# DSP2.net
KiCad netlist of a schematic drawn in Altium Designer
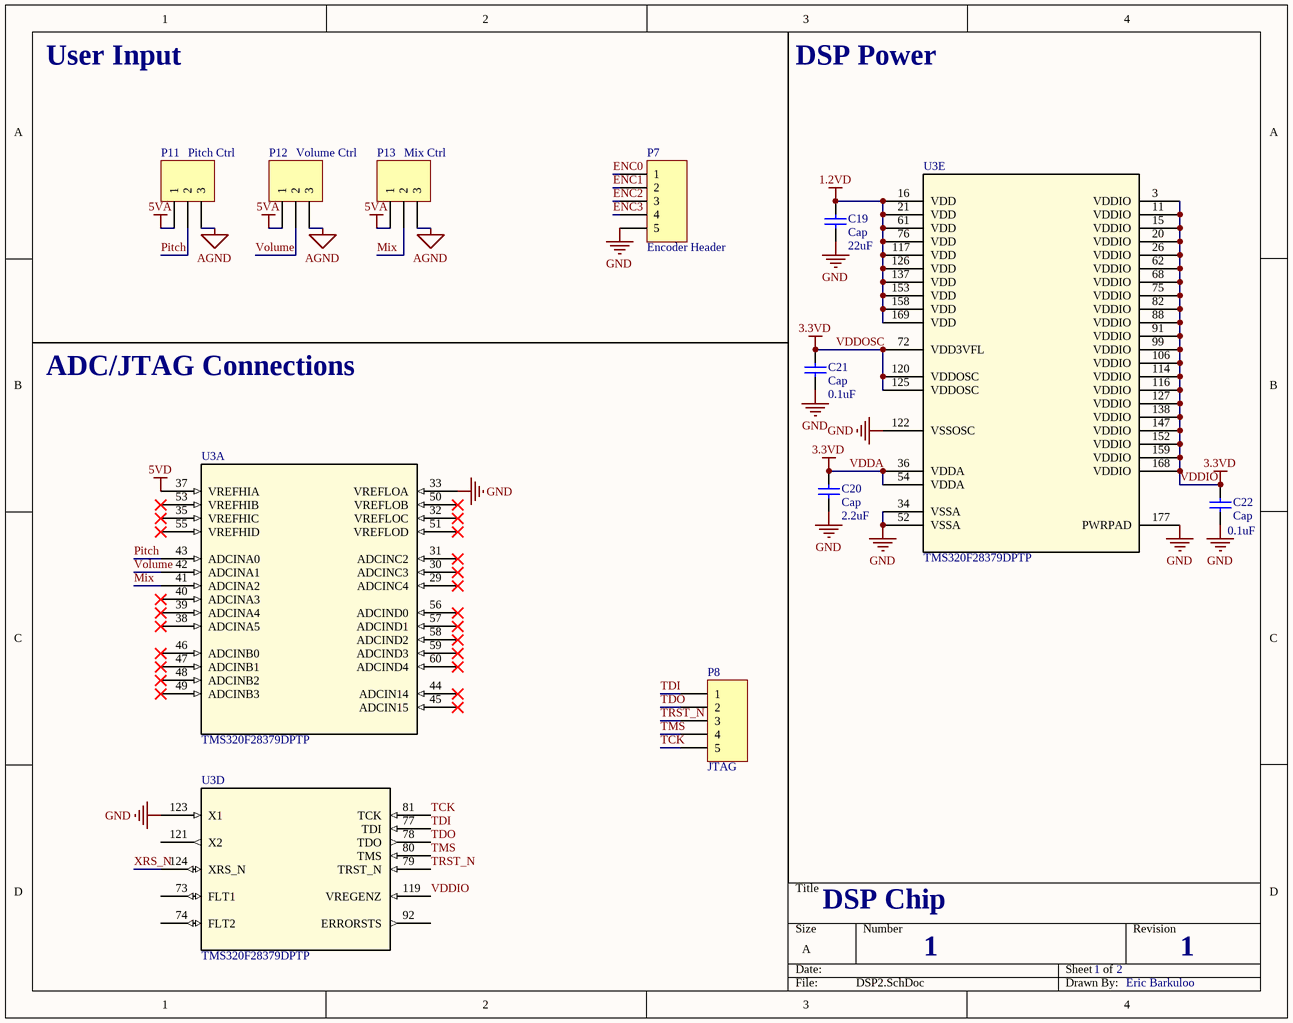
[diagram p0: DSP2.SchDoc]

(export (version "E")
  (design (tool "Eeschema 10.0.6"))
  (components
    (comp (ref "C19")
      (value "Cap")
      (footprint "Passives:CAPC0805")
      (description "Capacitor")
      (fields (field (name "ALTIUM_VALUE") "22uF") (field (name "PUBLISHER") "Altium Limited"))
      (libsource (lib "Miscellaneous Devices") (part "Cap"))
    )
    (comp (ref "C20")
      (value "Cap")
      (footprint "Passives:CAPC0805")
      (description "Capacitor")
      (fields (field (name "ALTIUM_VALUE") "2.2uF") (field (name "PUBLISHER") "Altium Limited"))
      (libsource (lib "Miscellaneous Devices") (part "Cap"))
    )
    (comp (ref "C21")
      (value "Cap")
      (footprint "Passives:CAPC0805")
      (description "Capacitor")
      (fields (field (name "ALTIUM_VALUE") "0.1uF") (field (name "PUBLISHER") "Altium Limited"))
      (libsource (lib "Miscellaneous Devices") (part "Cap"))
    )
    (comp (ref "C22")
      (value "Cap")
      (footprint "Passives:CAPC0805")
      (description "Capacitor")
      (fields (field (name "ALTIUM_VALUE") "0.1uF") (field (name "PUBLISHER") "Altium Limited"))
      (libsource (lib "Miscellaneous Devices") (part "Cap"))
    )
    (comp (ref "P7")
      (value "Encoder Header")
      (footprint "HDR1X5")
      (description "Header, 5-Pin")
      (fields (field (name "PUBLISHER") "Altium Limited"))
      (libsource (lib "Miscellaneous Connectors") (part "Header 5"))
    )
    (comp (ref "P8")
      (value "JTAG")
      (footprint "HDR1X5")
      (description "Header, 5-Pin")
      (fields (field (name "PUBLISHER") "Altium Limited"))
      (libsource (lib "Miscellaneous Connectors") (part "Header 5"))
    )
    (comp (ref "P11")
      (value "Pitch Ctrl")
      (footprint "HDR1X3")
      (description "Header, 3-Pin")
      (fields (field (name "PUBLISHER") "Altium Limited"))
      (libsource (lib "Miscellaneous Connectors") (part "Header 3"))
    )
    (comp (ref "P12")
      (value "Volume Ctrl")
      (footprint "HDR1X3")
      (description "Header, 3-Pin")
      (fields (field (name "PUBLISHER") "Altium Limited"))
      (libsource (lib "Miscellaneous Connectors") (part "Header 3"))
    )
    (comp (ref "P13")
      (value "Mix Ctrl")
      (footprint "HDR1X3")
      (description "Header, 3-Pin")
      (fields (field (name "PUBLISHER") "Altium Limited"))
      (libsource (lib "Miscellaneous Connectors") (part "Header 3"))
    )
    (comp (ref "U3")
      (value "TMS320F28379DPTP")
      (footprint "TMS320F28379DPTPT:PTP0176F_N")
      (description "Imported")
      (fields
        (field (name "PARTNUMBER") "TMS320F28379DPTPS")
        (field (name "MANUFACTURER") "Texas Instruments")
      )
      (libsource (lib "TMS320F28379DPTPT") (part "TMS320F28379DPTP"))
    )
  )
  (nets
    (net (code "1") (name "/ENC0") (class "Default")
      (node (ref "P7") (pin "1") (pinfunction "1_1") (pintype "passive"))
    )
    (net (code "2") (name "/ENC1") (class "Default")
      (node (ref "P7") (pin "2") (pinfunction "2_2") (pintype "passive"))
    )
    (net (code "3") (name "/ENC2") (class "Default")
      (node (ref "P7") (pin "3") (pinfunction "3_3") (pintype "passive"))
    )
    (net (code "4") (name "/ENC3") (class "Default")
      (node (ref "P7") (pin "4") (pinfunction "4_4") (pintype "passive"))
    )
    (net (code "5") (name "/Mix") (class "Default")
      (node (ref "P13") (pin "2") (pinfunction "2_2") (pintype "passive"))
      (node (ref "U3") (pin "41") (pinfunction "ADCINA2_41") (pintype "input"))
    )
    (net (code "6") (name "/Pitch") (class "Default")
      (node (ref "P11") (pin "2") (pinfunction "2_2") (pintype "passive"))
      (node (ref "U3") (pin "43") (pinfunction "ADCINA0_43") (pintype "input"))
    )
    (net (code "7") (name "/TCK") (class "Default")
      (node (ref "P8") (pin "5") (pinfunction "5_5") (pintype "passive"))
      (node (ref "U3") (pin "81") (pinfunction "TCK_81") (pintype "input"))
    )
    (net (code "8") (name "/TDI") (class "Default")
      (node (ref "P8") (pin "1") (pinfunction "1_1") (pintype "passive"))
      (node (ref "U3") (pin "77") (pinfunction "TDI_77") (pintype "input"))
    )
    (net (code "9") (name "/TDO") (class "Default")
      (node (ref "P8") (pin "2") (pinfunction "2_2") (pintype "passive"))
      (node (ref "U3") (pin "78") (pinfunction "TDO_78") (pintype "output"))
    )
    (net (code "10") (name "/TMS") (class "Default")
      (node (ref "P8") (pin "4") (pinfunction "4_4") (pintype "passive"))
      (node (ref "U3") (pin "80") (pinfunction "TMS_80") (pintype "input"))
    )
    (net (code "11") (name "/TRST_N") (class "Default")
      (node (ref "P8") (pin "3") (pinfunction "3_3") (pintype "passive"))
      (node (ref "U3") (pin "79") (pinfunction "TRST_N_79") (pintype "input"))
    )
    (net (code "12") (name "/Volume") (class "Default")
      (node (ref "P12") (pin "2") (pinfunction "2_2") (pintype "passive"))
      (node (ref "U3") (pin "42") (pinfunction "ADCINA1_42") (pintype "input"))
    )
    (net (code "13") (name "/XRS_N") (class "Default")
      (node (ref "U3") (pin "124") (pinfunction "XRS_N_124") (pintype "bidirectional"))
    )
    (net (code "14") (name "1.2VD") (class "Default")
      (node (ref "C19") (pin "2") (pinfunction "2_2") (pintype "passive"))
      (node (ref "U3") (pin "117") (pinfunction "VDD_117") (pintype "power_in"))
      (node (ref "U3") (pin "126") (pinfunction "VDD_126") (pintype "power_in"))
      (node (ref "U3") (pin "137") (pinfunction "VDD_137") (pintype "power_in"))
      (node (ref "U3") (pin "153") (pinfunction "VDD_153") (pintype "power_in"))
      (node (ref "U3") (pin "158") (pinfunction "VDD_158") (pintype "power_in"))
      (node (ref "U3") (pin "16") (pinfunction "VDD_16") (pintype "power_in"))
      (node (ref "U3") (pin "169") (pinfunction "VDD_169") (pintype "power_in"))
      (node (ref "U3") (pin "21") (pinfunction "VDD_21") (pintype "power_in"))
      (node (ref "U3") (pin "61") (pinfunction "VDD_61") (pintype "power_in"))
      (node (ref "U3") (pin "76") (pinfunction "VDD_76") (pintype "power_in"))
    )
    (net (code "15") (name "3.3VD") (class "Default")
      (node (ref "C20") (pin "2") (pinfunction "2_2") (pintype "passive"))
      (node (ref "C21") (pin "2") (pinfunction "2_2") (pintype "passive"))
      (node (ref "C22") (pin "2") (pinfunction "2_2") (pintype "passive"))
      (node (ref "U3") (pin "106") (pinfunction "VDDIO_106") (pintype "power_in"))
      (node (ref "U3") (pin "11") (pinfunction "VDDIO_11") (pintype "power_in"))
      (node (ref "U3") (pin "114") (pinfunction "VDDIO_114") (pintype "power_in"))
      (node (ref "U3") (pin "116") (pinfunction "VDDIO_116") (pintype "power_in"))
      (node (ref "U3") (pin "119") (pinfunction "VREGENZ_119") (pintype "input"))
      (node (ref "U3") (pin "120") (pinfunction "VDDOSC_120") (pintype "power_in"))
      (node (ref "U3") (pin "125") (pinfunction "VDDOSC_125") (pintype "power_in"))
      (node (ref "U3") (pin "127") (pinfunction "VDDIO_127") (pintype "power_in"))
      (node (ref "U3") (pin "138") (pinfunction "VDDIO_138") (pintype "power_in"))
      (node (ref "U3") (pin "147") (pinfunction "VDDIO_147") (pintype "power_in"))
      (node (ref "U3") (pin "15") (pinfunction "VDDIO_15") (pintype "power_in"))
      (node (ref "U3") (pin "152") (pinfunction "VDDIO_152") (pintype "power_in"))
      (node (ref "U3") (pin "159") (pinfunction "VDDIO_159") (pintype "power_in"))
      (node (ref "U3") (pin "168") (pinfunction "VDDIO_168") (pintype "power_in"))
      (node (ref "U3") (pin "20") (pinfunction "VDDIO_20") (pintype "power_in"))
      (node (ref "U3") (pin "26") (pinfunction "VDDIO_26") (pintype "power_in"))
      (node (ref "U3") (pin "3") (pinfunction "VDDIO_3") (pintype "power_in"))
      (node (ref "U3") (pin "36") (pinfunction "VDDA_36") (pintype "power_in"))
      (node (ref "U3") (pin "54") (pinfunction "VDDA_54") (pintype "power_in"))
      (node (ref "U3") (pin "62") (pinfunction "VDDIO_62") (pintype "power_in"))
      (node (ref "U3") (pin "68") (pinfunction "VDDIO_68") (pintype "power_in"))
      (node (ref "U3") (pin "72") (pinfunction "VDD3VFL_72") (pintype "power_in"))
      (node (ref "U3") (pin "75") (pinfunction "VDDIO_75") (pintype "power_in"))
      (node (ref "U3") (pin "82") (pinfunction "VDDIO_82") (pintype "power_in"))
      (node (ref "U3") (pin "88") (pinfunction "VDDIO_88") (pintype "power_in"))
      (node (ref "U3") (pin "91") (pinfunction "VDDIO_91") (pintype "power_in"))
      (node (ref "U3") (pin "99") (pinfunction "VDDIO_99") (pintype "power_in"))
    )
    (net (code "16") (name "5VA") (class "Default")
      (node (ref "P11") (pin "1") (pinfunction "1_1") (pintype "passive"))
      (node (ref "P12") (pin "1") (pinfunction "1_1") (pintype "passive"))
      (node (ref "P13") (pin "1") (pinfunction "1_1") (pintype "passive"))
    )
    (net (code "17") (name "5VD") (class "Default")
      (node (ref "U3") (pin "37") (pinfunction "VREFHIA_37") (pintype "input"))
    )
    (net (code "18") (name "AGND") (class "Default")
      (node (ref "P11") (pin "3") (pinfunction "3_3") (pintype "passive"))
      (node (ref "P12") (pin "3") (pinfunction "3_3") (pintype "passive"))
      (node (ref "P13") (pin "3") (pinfunction "3_3") (pintype "passive"))
    )
    (net (code "19") (name "GND") (class "Default")
      (node (ref "C19") (pin "1") (pinfunction "1_1") (pintype "passive"))
      (node (ref "C20") (pin "1") (pinfunction "1_1") (pintype "passive"))
      (node (ref "C21") (pin "1") (pinfunction "1_1") (pintype "passive"))
      (node (ref "C22") (pin "1") (pinfunction "1_1") (pintype "passive"))
      (node (ref "P7") (pin "5") (pinfunction "5_5") (pintype "passive"))
      (node (ref "U3") (pin "122") (pinfunction "VSSOSC_122") (pintype "power_in"))
      (node (ref "U3") (pin "123") (pinfunction "X1_123") (pintype "input"))
      (node (ref "U3") (pin "177") (pinfunction "PWRPAD_177") (pintype "power_in"))
      (node (ref "U3") (pin "33") (pinfunction "VREFLOA_33") (pintype "input"))
      (node (ref "U3") (pin "34") (pinfunction "VSSA_34") (pintype "power_in"))
      (node (ref "U3") (pin "52") (pinfunction "VSSA_52") (pintype "power_in"))
    )
    (net (code "20") (name "unconnected-(U3A-ADCIN14-Pad44)") (class "Default")
      (node (ref "U3") (pin "44") (pinfunction "ADCIN14_44") (pintype "input+no_connect"))
    )
    (net (code "21") (name "unconnected-(U3A-ADCIN15-Pad45)") (class "Default")
      (node (ref "U3") (pin "45") (pinfunction "ADCIN15_45") (pintype "input+no_connect"))
    )
    (net (code "22") (name "unconnected-(U3A-ADCINA3-Pad40)") (class "Default")
      (node (ref "U3") (pin "40") (pinfunction "ADCINA3_40") (pintype "input+no_connect"))
    )
    (net (code "23") (name "unconnected-(U3A-ADCINA4-Pad39)") (class "Default")
      (node (ref "U3") (pin "39") (pinfunction "ADCINA4_39") (pintype "input+no_connect"))
    )
    (net (code "24") (name "unconnected-(U3A-ADCINA5-Pad38)") (class "Default")
      (node (ref "U3") (pin "38") (pinfunction "ADCINA5_38") (pintype "input+no_connect"))
    )
    (net (code "25") (name "unconnected-(U3A-ADCINB0-Pad46)") (class "Default")
      (node (ref "U3") (pin "46") (pinfunction "ADCINB0_46") (pintype "input+no_connect"))
    )
    (net (code "26") (name "unconnected-(U3A-ADCINB1-Pad47)") (class "Default")
      (node (ref "U3") (pin "47") (pinfunction "ADCINB1_47") (pintype "input+no_connect"))
    )
    (net (code "27") (name "unconnected-(U3A-ADCINB2-Pad48)") (class "Default")
      (node (ref "U3") (pin "48") (pinfunction "ADCINB2_48") (pintype "input+no_connect"))
    )
    (net (code "28") (name "unconnected-(U3A-ADCINB3-Pad49)") (class "Default")
      (node (ref "U3") (pin "49") (pinfunction "ADCINB3_49") (pintype "input+no_connect"))
    )
    (net (code "29") (name "unconnected-(U3A-ADCINC2-Pad31)") (class "Default")
      (node (ref "U3") (pin "31") (pinfunction "ADCINC2_31") (pintype "input+no_connect"))
    )
    (net (code "30") (name "unconnected-(U3A-ADCINC3-Pad30)") (class "Default")
      (node (ref "U3") (pin "30") (pinfunction "ADCINC3_30") (pintype "input+no_connect"))
    )
    (net (code "31") (name "unconnected-(U3A-ADCINC4-Pad29)") (class "Default")
      (node (ref "U3") (pin "29") (pinfunction "ADCINC4_29") (pintype "input+no_connect"))
    )
    (net (code "32") (name "unconnected-(U3A-ADCIND0-Pad56)") (class "Default")
      (node (ref "U3") (pin "56") (pinfunction "ADCIND0_56") (pintype "input+no_connect"))
    )
    (net (code "33") (name "unconnected-(U3A-ADCIND1-Pad57)") (class "Default")
      (node (ref "U3") (pin "57") (pinfunction "ADCIND1_57") (pintype "input+no_connect"))
    )
    (net (code "34") (name "unconnected-(U3A-ADCIND2-Pad58)") (class "Default")
      (node (ref "U3") (pin "58") (pinfunction "ADCIND2_58") (pintype "input+no_connect"))
    )
    (net (code "35") (name "unconnected-(U3A-ADCIND3-Pad59)") (class "Default")
      (node (ref "U3") (pin "59") (pinfunction "ADCIND3_59") (pintype "input+no_connect"))
    )
    (net (code "36") (name "unconnected-(U3A-ADCIND4-Pad60)") (class "Default")
      (node (ref "U3") (pin "60") (pinfunction "ADCIND4_60") (pintype "input+no_connect"))
    )
    (net (code "37") (name "unconnected-(U3A-VREFHIB-Pad53)") (class "Default")
      (node (ref "U3") (pin "53") (pinfunction "VREFHIB_53") (pintype "input+no_connect"))
    )
    (net (code "38") (name "unconnected-(U3A-VREFHIC-Pad35)") (class "Default")
      (node (ref "U3") (pin "35") (pinfunction "VREFHIC_35") (pintype "input+no_connect"))
    )
    (net (code "39") (name "unconnected-(U3A-VREFHID-Pad55)") (class "Default")
      (node (ref "U3") (pin "55") (pinfunction "VREFHID_55") (pintype "input+no_connect"))
    )
    (net (code "40") (name "unconnected-(U3A-VREFLOB-Pad50)") (class "Default")
      (node (ref "U3") (pin "50") (pinfunction "VREFLOB_50") (pintype "input+no_connect"))
    )
    (net (code "41") (name "unconnected-(U3A-VREFLOC-Pad32)") (class "Default")
      (node (ref "U3") (pin "32") (pinfunction "VREFLOC_32") (pintype "input+no_connect"))
    )
    (net (code "42") (name "unconnected-(U3A-VREFLOD-Pad51)") (class "Default")
      (node (ref "U3") (pin "51") (pinfunction "VREFLOD_51") (pintype "input+no_connect"))
    )
    (net (code "43") (name "unconnected-(U3D-ERRORSTS-Pad92)") (class "Default")
      (node (ref "U3") (pin "92") (pinfunction "ERRORSTS_92") (pintype "output"))
    )
    (net (code "44") (name "unconnected-(U3D-FLT1-Pad73)") (class "Default")
      (node (ref "U3") (pin "73") (pinfunction "FLT1_73") (pintype "bidirectional"))
    )
    (net (code "45") (name "unconnected-(U3D-FLT2-Pad74)") (class "Default")
      (node (ref "U3") (pin "74") (pinfunction "FLT2_74") (pintype "bidirectional"))
    )
    (net (code "46") (name "unconnected-(U3D-X2-Pad121)") (class "Default")
      (node (ref "U3") (pin "121") (pinfunction "X2_121") (pintype "output"))
    )
  )
)
